# DCC-light.net
KiCad netlist of a schematic drawn in EAGLE
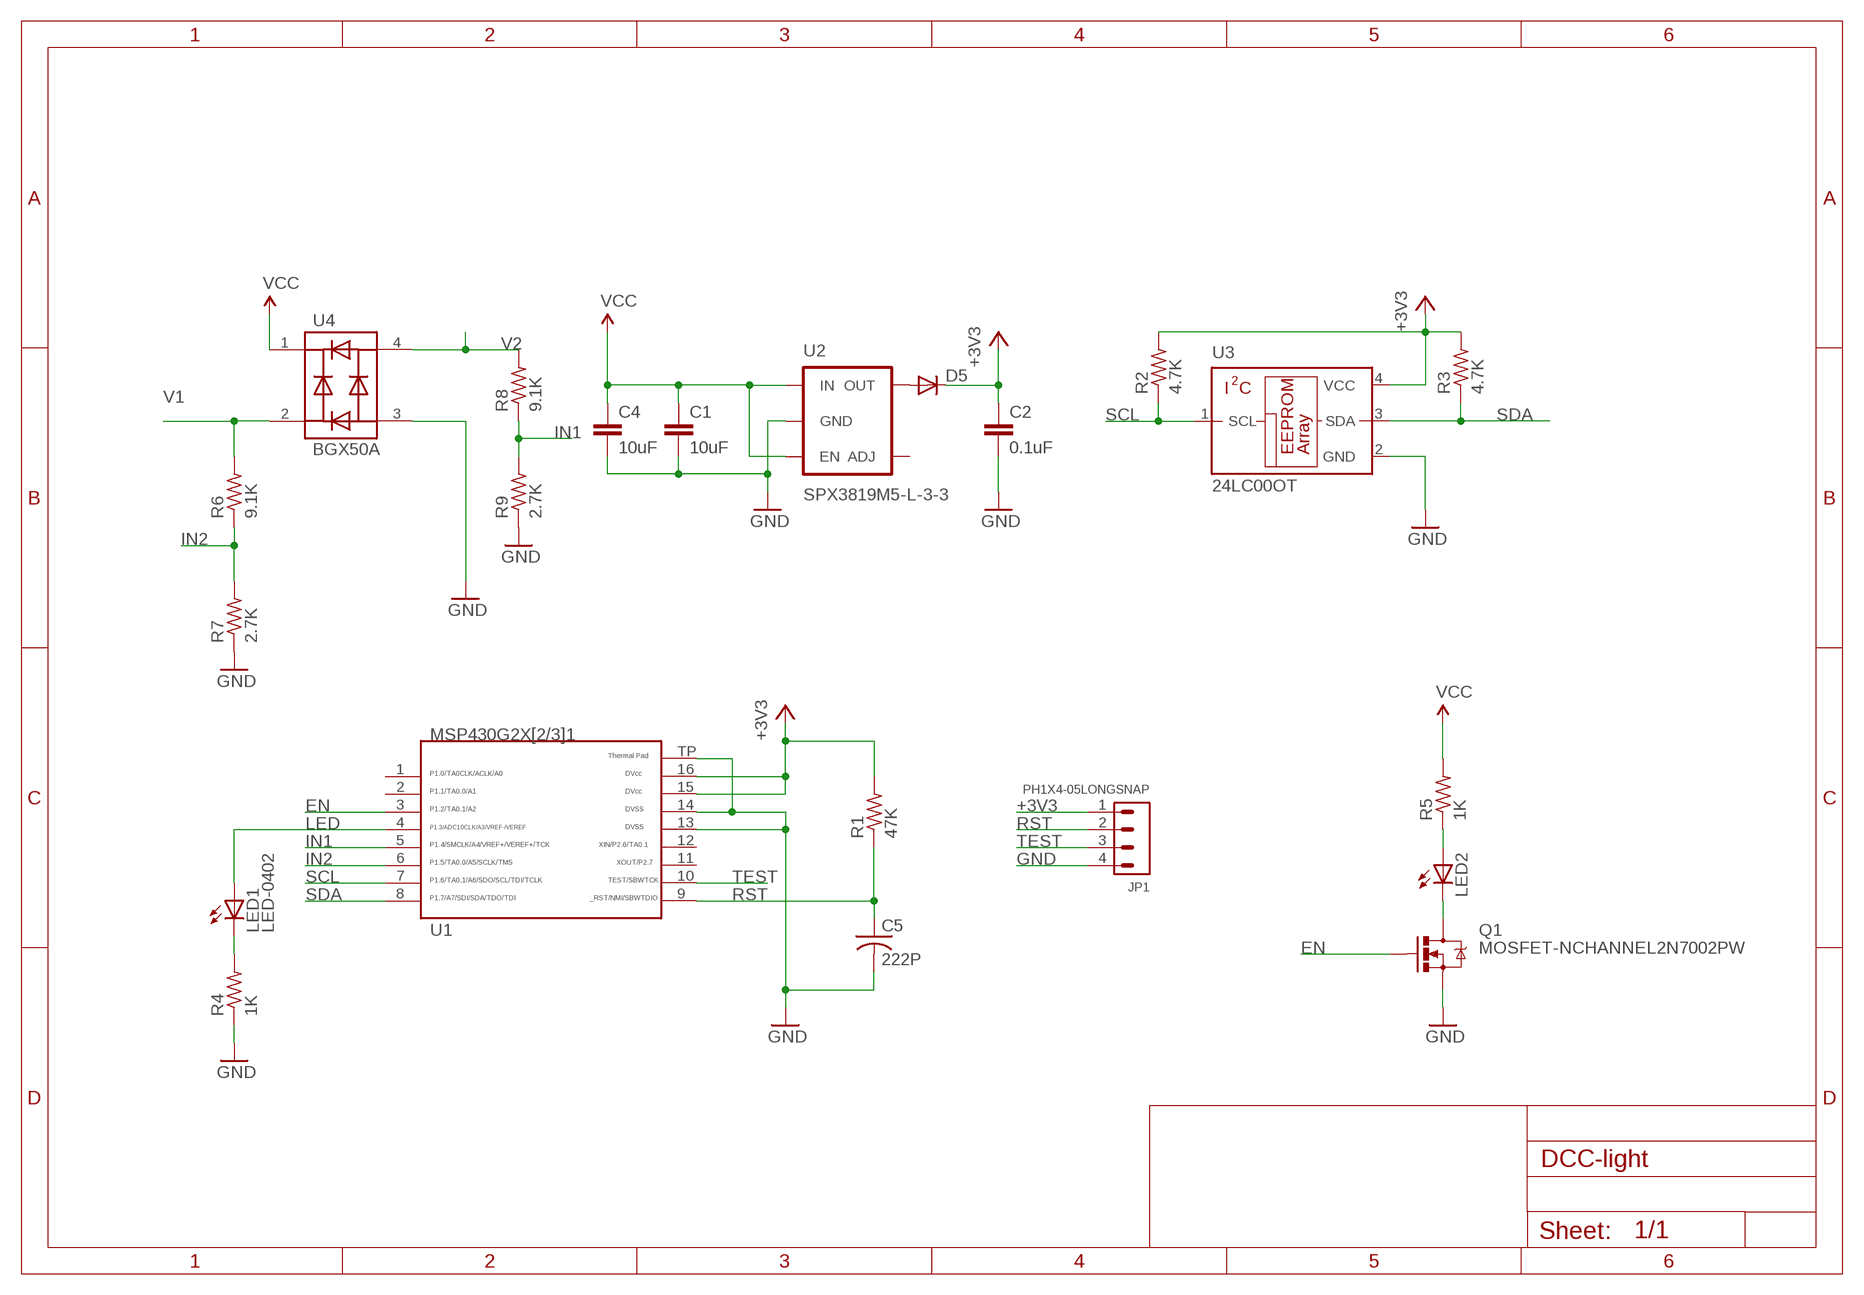
[diagram p0: schematic, sheet 1]

(export (version "E")
  (design (tool "Eeschema 10.0.6"))
  (components
    (comp (ref "C1")
      (value "10uF")
      (footprint "eagle-import:0402-CAP")
      (libsource (lib "eagle-import") (part "CAP0402-CAP"))
    )
    (comp (ref "C2")
      (value "0.1uF")
      (footprint "eagle-import:0603-CAP")
      (libsource (lib "eagle-import") (part "CAP0603-CAP"))
    )
    (comp (ref "C4")
      (value "10uF")
      (footprint "eagle-import:0603-CAP")
      (libsource (lib "eagle-import") (part "CAP0603-CAP"))
    )
    (comp (ref "C5")
      (value "222P")
      (footprint "eagle-import:C0402")
      (libsource (lib "eagle-import") (part "C-USC0402"))
    )
    (comp (ref "D5")
      (value "DIODE-SOD523")
      (footprint "eagle-import:SOD523")
      (libsource (lib "eagle-import") (part "DIODE-SOD523"))
    )
    (comp (ref "JP1")
      (value "PH1X4-05LONGSNAP")
      (footprint "eagle-import:PHLS005-1-4")
      (libsource (lib "eagle-import") (part "PH1X4-05LONGSNAP"))
    )
    (comp (ref "LED1")
      (value "LED-0402")
      (footprint "eagle-import:0402-LED")
      (libsource (lib "eagle-import") (part "LED-0402"))
    )
    (comp (ref "LED2")
      (value "LEDSMT1206")
      (footprint "eagle-import:1206")
      (libsource (lib "eagle-import") (part "LEDSMT1206"))
    )
    (comp (ref "Q1")
      (value "MOSFET-NCHANNEL2N7002PW")
      (footprint "eagle-import:SOT323")
      (libsource (lib "eagle-import") (part "MOSFET-NCHANNEL2N7002PW"))
    )
    (comp (ref "R1")
      (value "47K")
      (footprint "eagle-import:R0402")
      (libsource (lib "eagle-import") (part "R-US_R0402"))
    )
    (comp (ref "R2")
      (value "4.7K")
      (footprint "eagle-import:R0402")
      (libsource (lib "eagle-import") (part "R-US_R0402"))
    )
    (comp (ref "R3")
      (value "4.7K")
      (footprint "eagle-import:R0402")
      (libsource (lib "eagle-import") (part "R-US_R0402"))
    )
    (comp (ref "R4")
      (value "1K")
      (footprint "eagle-import:R0402")
      (libsource (lib "eagle-import") (part "R-US_R0402"))
    )
    (comp (ref "R5")
      (value "1K")
      (footprint "eagle-import:R0603")
      (libsource (lib "eagle-import") (part "R-US_R0603"))
    )
    (comp (ref "R6")
      (value "9.1K")
      (footprint "eagle-import:R0402")
      (libsource (lib "eagle-import") (part "R-US_R0402"))
    )
    (comp (ref "R7")
      (value "2.7K")
      (footprint "eagle-import:R0402")
      (libsource (lib "eagle-import") (part "R-US_R0402"))
    )
    (comp (ref "R8")
      (value "9.1K")
      (footprint "eagle-import:R0402")
      (libsource (lib "eagle-import") (part "R-US_R0402"))
    )
    (comp (ref "R9")
      (value "2.7K")
      (footprint "eagle-import:R0402")
      (libsource (lib "eagle-import") (part "R-US_R0402"))
    )
    (comp (ref "U1")
      (value "G2X[2/3]1---RSA16")
      (footprint "eagle-import:RSA16")
      (libsource (lib "eagle-import") (part "G2X[2/3]1---RSA16"))
    )
    (comp (ref "U2")
      (value "SPX3819M5-L-3-3")
      (footprint "eagle-import:SOT23-5")
      (libsource (lib "eagle-import") (part "AP2202-ADJ"))
    )
    (comp (ref "U3")
      (value "24LC00OT")
      (footprint "eagle-import:SOT23-5L")
      (fields (field (name "MF") "MICROCHIP") (field (name "MPN") "24LC00T-I/OT"))
      (libsource (lib "eagle-import") (part "2400OTLC"))
    )
    (comp (ref "U4")
      (value "BGX50A")
      (footprint "eagle-import:SOT143")
      (libsource (lib "eagle-import") (part "BGX50A"))
    )
  )
  (nets
    (net (code "1") (name "+3V3") (class "Default")
      (node (ref "C2") (pin "1") (pinfunction "1_1") (pintype "passive"))
      (node (ref "D5") (pin "C") (pinfunction "C_C") (pintype "passive"))
      (node (ref "JP1") (pin "1") (pinfunction "1_1") (pintype "bidirectional"))
      (node (ref "R1") (pin "2") (pinfunction "2_2") (pintype "passive"))
      (node (ref "R2") (pin "2") (pinfunction "2_2") (pintype "passive"))
      (node (ref "R3") (pin "2") (pinfunction "2_2") (pintype "passive"))
      (node (ref "U1") (pin "15") (pinfunction "15_15") (pintype "bidirectional"))
      (node (ref "U1") (pin "16") (pinfunction "16_16") (pintype "bidirectional"))
      (node (ref "U3") (pin "4") (pinfunction "VCC_4") (pintype "power_in"))
    )
    (net (code "2") (name "/EN") (class "Default")
      (node (ref "Q1") (pin "1") (pinfunction "G_1") (pintype "passive"))
      (node (ref "U1") (pin "3") (pinfunction "3_3") (pintype "bidirectional"))
    )
    (net (code "3") (name "/IN1") (class "Default")
      (node (ref "R8") (pin "1") (pinfunction "1_1") (pintype "passive"))
      (node (ref "R9") (pin "2") (pinfunction "2_2") (pintype "passive"))
      (node (ref "U1") (pin "5") (pinfunction "5_5") (pintype "bidirectional"))
    )
    (net (code "4") (name "/IN2") (class "Default")
      (node (ref "R6") (pin "1") (pinfunction "1_1") (pintype "passive"))
      (node (ref "R7") (pin "2") (pinfunction "2_2") (pintype "passive"))
      (node (ref "U1") (pin "6") (pinfunction "6_6") (pintype "bidirectional"))
    )
    (net (code "5") (name "/LED") (class "Default")
      (node (ref "LED1") (pin "A") (pinfunction "A_A") (pintype "passive"))
      (node (ref "U1") (pin "4") (pinfunction "4_4") (pintype "bidirectional"))
    )
    (net (code "6") (name "/RST") (class "Default")
      (node (ref "C5") (pin "1") (pinfunction "1_1") (pintype "passive"))
      (node (ref "JP1") (pin "2") (pinfunction "2_2") (pintype "bidirectional"))
      (node (ref "R1") (pin "1") (pinfunction "1_1") (pintype "passive"))
      (node (ref "U1") (pin "9") (pinfunction "9_9") (pintype "bidirectional"))
    )
    (net (code "7") (name "/SCL") (class "Default")
      (node (ref "R2") (pin "1") (pinfunction "1_1") (pintype "passive"))
      (node (ref "U1") (pin "7") (pinfunction "7_7") (pintype "bidirectional"))
      (node (ref "U3") (pin "1") (pinfunction "SCL_1") (pintype "input"))
    )
    (net (code "8") (name "/SDA") (class "Default")
      (node (ref "R3") (pin "1") (pinfunction "1_1") (pintype "passive"))
      (node (ref "U1") (pin "8") (pinfunction "8_8") (pintype "bidirectional"))
      (node (ref "U3") (pin "3") (pinfunction "SDA_3") (pintype "bidirectional"))
    )
    (net (code "9") (name "/TEST") (class "Default")
      (node (ref "JP1") (pin "3") (pinfunction "3_3") (pintype "bidirectional"))
      (node (ref "U1") (pin "10") (pinfunction "10_10") (pintype "bidirectional"))
    )
    (net (code "10") (name "/V1") (class "Default")
      (node (ref "R6") (pin "2") (pinfunction "2_2") (pintype "passive"))
      (node (ref "U4") (pin "2") (pinfunction "2_2") (pintype "bidirectional"))
    )
    (net (code "11") (name "/V2") (class "Default")
      (node (ref "R8") (pin "2") (pinfunction "2_2") (pintype "passive"))
      (node (ref "U4") (pin "4") (pinfunction "4_4") (pintype "bidirectional"))
    )
    (net (code "12") (name "GND") (class "Default")
      (node (ref "C1") (pin "2") (pinfunction "2_2") (pintype "passive"))
      (node (ref "C2") (pin "2") (pinfunction "2_2") (pintype "passive"))
      (node (ref "C4") (pin "2") (pinfunction "2_2") (pintype "passive"))
      (node (ref "C5") (pin "2") (pinfunction "2_2") (pintype "passive"))
      (node (ref "JP1") (pin "4") (pinfunction "4_4") (pintype "bidirectional"))
      (node (ref "Q1") (pin "2") (pinfunction "S_2") (pintype "passive"))
      (node (ref "R4") (pin "1") (pinfunction "1_1") (pintype "passive"))
      (node (ref "R7") (pin "1") (pinfunction "1_1") (pintype "passive"))
      (node (ref "R9") (pin "1") (pinfunction "1_1") (pintype "passive"))
      (node (ref "U1") (pin "13") (pinfunction "13_13") (pintype "bidirectional"))
      (node (ref "U1") (pin "14") (pinfunction "14_14") (pintype "bidirectional"))
      (node (ref "U1") (pin "TP") (pinfunction "TP_TP") (pintype "bidirectional"))
      (node (ref "U2") (pin "2") (pinfunction "GND_2") (pintype "input"))
      (node (ref "U3") (pin "2") (pinfunction "GND_2") (pintype "power_in"))
      (node (ref "U4") (pin "3") (pinfunction "3_3") (pintype "bidirectional"))
    )
    (net (code "13") (name "Net-(LED1-PadC)") (class "Default")
      (node (ref "LED1") (pin "C") (pinfunction "C_C") (pintype "passive"))
      (node (ref "R4") (pin "2") (pinfunction "2_2") (pintype "passive"))
    )
    (net (code "14") (name "Net-(LED2-PadA)") (class "Default")
      (node (ref "LED2") (pin "A") (pinfunction "A_A") (pintype "passive"))
      (node (ref "R5") (pin "1") (pinfunction "1_1") (pintype "passive"))
    )
    (net (code "15") (name "Net-(Q1-D)") (class "Default")
      (node (ref "LED2") (pin "C") (pinfunction "C_C") (pintype "passive"))
      (node (ref "Q1") (pin "3") (pinfunction "D_3") (pintype "passive"))
    )
    (net (code "16") (name "Net-(U2-OUT)") (class "Default")
      (node (ref "D5") (pin "A") (pinfunction "A_A") (pintype "passive"))
      (node (ref "U2") (pin "5") (pinfunction "OUT_5") (pintype "passive"))
    )
    (net (code "17") (name "VCC") (class "Default")
      (node (ref "C1") (pin "1") (pinfunction "1_1") (pintype "passive"))
      (node (ref "C4") (pin "1") (pinfunction "1_1") (pintype "passive"))
      (node (ref "R5") (pin "2") (pinfunction "2_2") (pintype "passive"))
      (node (ref "U2") (pin "1") (pinfunction "IN_1") (pintype "input"))
      (node (ref "U2") (pin "3") (pinfunction "EN_3") (pintype "input"))
      (node (ref "U4") (pin "1") (pinfunction "1_1") (pintype "bidirectional"))
    )
    (net (code "18") (name "unconnected-(U1-Pad1)") (class "Default")
      (node (ref "U1") (pin "1") (pinfunction "1_1") (pintype "bidirectional"))
    )
    (net (code "19") (name "unconnected-(U1-Pad2)") (class "Default")
      (node (ref "U1") (pin "2") (pinfunction "2_2") (pintype "bidirectional"))
    )
    (net (code "20") (name "unconnected-(U1-Pad11)") (class "Default")
      (node (ref "U1") (pin "11") (pinfunction "11_11") (pintype "bidirectional"))
    )
    (net (code "21") (name "unconnected-(U1-Pad12)") (class "Default")
      (node (ref "U1") (pin "12") (pinfunction "12_12") (pintype "bidirectional"))
    )
    (net (code "22") (name "unconnected-(U2-ADJ-Pad4)") (class "Default")
      (node (ref "U2") (pin "4") (pinfunction "ADJ_4") (pintype "input"))
    )
  )
)
